# PGTN021_octasource2b_controls.net
KiCad netlist of a schematic drawn in EAGLE
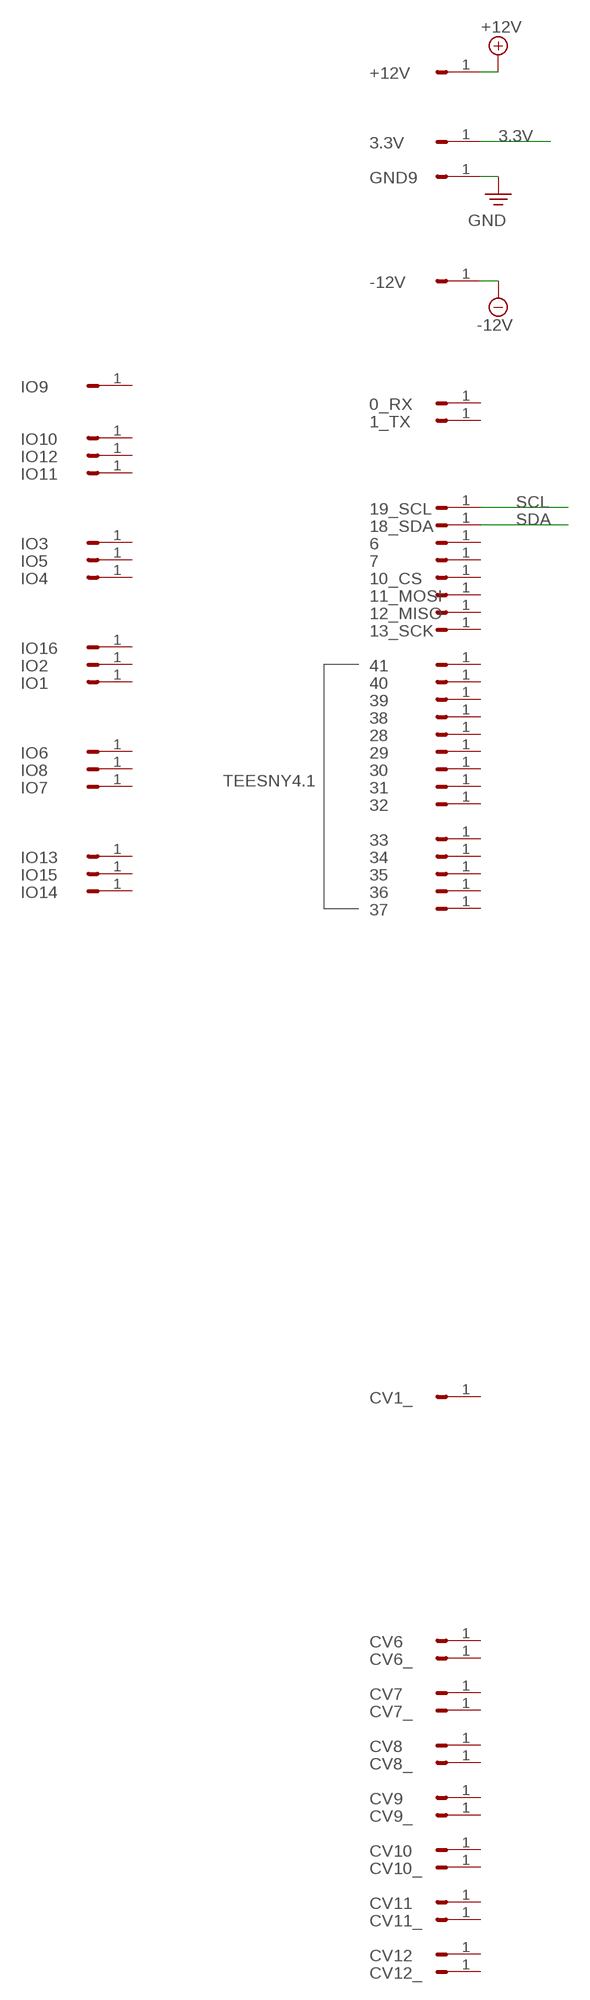
[diagram p0: schematic, sheet 1, part 1 of 2]
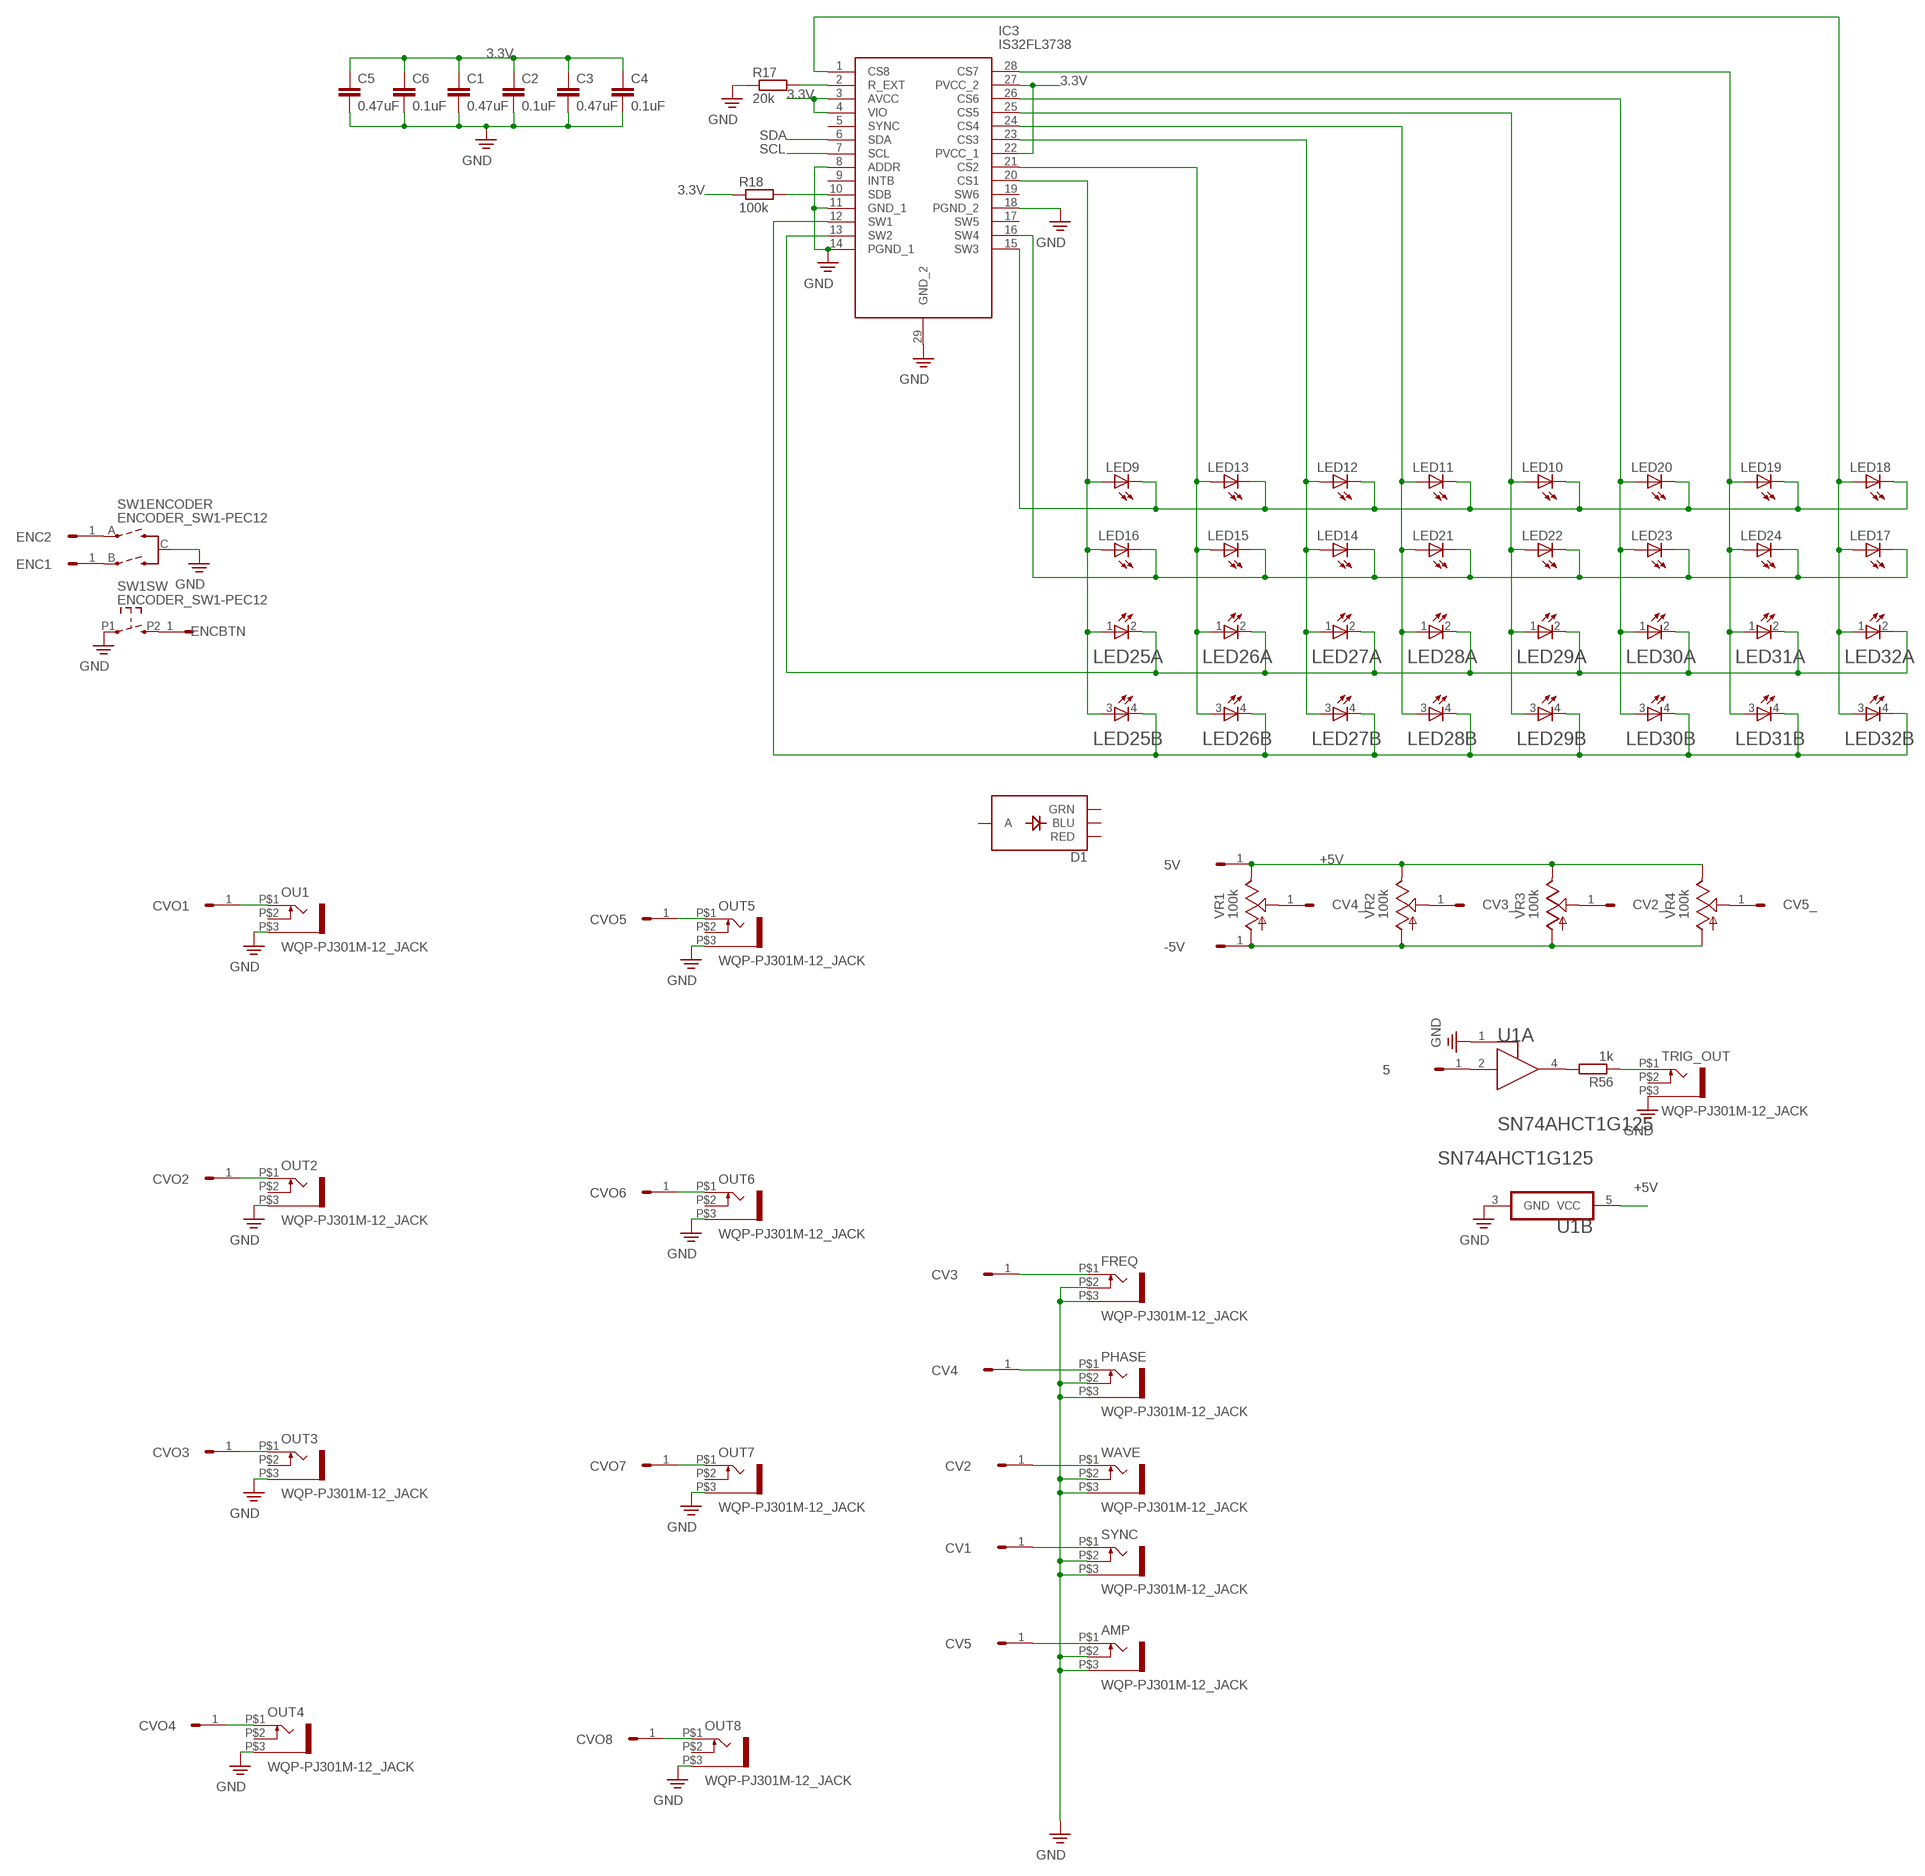
[diagram p1: schematic, sheet 1, part 2 of 2]

(export (version "E")
  (design (tool "Eeschema 10.0.6"))
  (components
    (comp (ref "+12V")
      (value "HEADER/MALE/01")
      (footprint "eagle-import:HEADER_MALE_01")
      (fields (field (name "SPICEPREFIX") "X"))
      (libsource (lib "eagle-import") (part "HEADER/MALE/01"))
    )
    (comp (ref "-5V")
      (value "HEADER/MALE/01")
      (footprint "eagle-import:HEADER_MALE_01")
      (fields (field (name "SPICEPREFIX") "X"))
      (libsource (lib "eagle-import") (part "HEADER/MALE/01"))
    )
    (comp (ref "-12V")
      (value "HEADER/MALE/01")
      (footprint "eagle-import:HEADER_MALE_01")
      (fields (field (name "SPICEPREFIX") "X"))
      (libsource (lib "eagle-import") (part "HEADER/MALE/01"))
    )
    (comp (ref "0_RX")
      (value "HEADER/MALE/01")
      (footprint "eagle-import:HEADER_MALE_01")
      (fields (field (name "SPICEPREFIX") "X"))
      (libsource (lib "eagle-import") (part "HEADER/MALE/01"))
    )
    (comp (ref "1_TX")
      (value "HEADER/MALE/01")
      (footprint "eagle-import:HEADER_MALE_01")
      (fields (field (name "SPICEPREFIX") "X"))
      (libsource (lib "eagle-import") (part "HEADER/MALE/01"))
    )
    (comp (ref "3.3V")
      (value "HEADER/MALE/01")
      (footprint "eagle-import:HEADER_MALE_01")
      (fields (field (name "SPICEPREFIX") "X"))
      (libsource (lib "eagle-import") (part "HEADER/MALE/01"))
    )
    (comp (ref "5")
      (value "HEADER/MALE/01")
      (footprint "eagle-import:HEADER_MALE_01")
      (fields (field (name "SPICEPREFIX") "X"))
      (libsource (lib "eagle-import") (part "HEADER/MALE/01"))
    )
    (comp (ref "5V")
      (value "HEADER/MALE/01")
      (footprint "eagle-import:HEADER_MALE_01")
      (fields (field (name "SPICEPREFIX") "X"))
      (libsource (lib "eagle-import") (part "HEADER/MALE/01"))
    )
    (comp (ref "6")
      (value "HEADER/MALE/01")
      (footprint "eagle-import:HEADER_MALE_01")
      (fields (field (name "SPICEPREFIX") "X"))
      (libsource (lib "eagle-import") (part "HEADER/MALE/01"))
    )
    (comp (ref "7")
      (value "HEADER/MALE/01")
      (footprint "eagle-import:HEADER_MALE_01")
      (fields (field (name "SPICEPREFIX") "X"))
      (libsource (lib "eagle-import") (part "HEADER/MALE/01"))
    )
    (comp (ref "10_CS")
      (value "HEADER/MALE/01")
      (footprint "eagle-import:HEADER_MALE_01")
      (fields (field (name "SPICEPREFIX") "X"))
      (libsource (lib "eagle-import") (part "HEADER/MALE/01"))
    )
    (comp (ref "11_MOSI")
      (value "HEADER/MALE/01")
      (footprint "eagle-import:HEADER_MALE_01")
      (fields (field (name "SPICEPREFIX") "X"))
      (libsource (lib "eagle-import") (part "HEADER/MALE/01"))
    )
    (comp (ref "12_MISO")
      (value "HEADER/MALE/01")
      (footprint "eagle-import:HEADER_MALE_01")
      (fields (field (name "SPICEPREFIX") "X"))
      (libsource (lib "eagle-import") (part "HEADER/MALE/01"))
    )
    (comp (ref "13_SCK")
      (value "HEADER/MALE/01")
      (footprint "eagle-import:HEADER_MALE_01")
      (fields (field (name "SPICEPREFIX") "X"))
      (libsource (lib "eagle-import") (part "HEADER/MALE/01"))
    )
    (comp (ref "18_SDA")
      (value "HEADER/MALE/01")
      (footprint "eagle-import:HEADER_MALE_01")
      (fields (field (name "SPICEPREFIX") "X"))
      (libsource (lib "eagle-import") (part "HEADER/MALE/01"))
    )
    (comp (ref "19_SCL")
      (value "HEADER/MALE/01")
      (footprint "eagle-import:HEADER_MALE_01")
      (fields (field (name "SPICEPREFIX") "X"))
      (libsource (lib "eagle-import") (part "HEADER/MALE/01"))
    )
    (comp (ref "28")
      (value "HEADER/MALE/01")
      (footprint "eagle-import:HEADER_MALE_01")
      (fields (field (name "SPICEPREFIX") "X"))
      (libsource (lib "eagle-import") (part "HEADER/MALE/01"))
    )
    (comp (ref "29")
      (value "HEADER/MALE/01")
      (footprint "eagle-import:HEADER_MALE_01")
      (fields (field (name "SPICEPREFIX") "X"))
      (libsource (lib "eagle-import") (part "HEADER/MALE/01"))
    )
    (comp (ref "30")
      (value "HEADER/MALE/01")
      (footprint "eagle-import:HEADER_MALE_01")
      (fields (field (name "SPICEPREFIX") "X"))
      (libsource (lib "eagle-import") (part "HEADER/MALE/01"))
    )
    (comp (ref "31")
      (value "HEADER/MALE/01")
      (footprint "eagle-import:HEADER_MALE_01")
      (fields (field (name "SPICEPREFIX") "X"))
      (libsource (lib "eagle-import") (part "HEADER/MALE/01"))
    )
    (comp (ref "32")
      (value "HEADER/MALE/01")
      (footprint "eagle-import:HEADER_MALE_01")
      (fields (field (name "SPICEPREFIX") "X"))
      (libsource (lib "eagle-import") (part "HEADER/MALE/01"))
    )
    (comp (ref "33")
      (value "HEADER/MALE/01")
      (footprint "eagle-import:HEADER_MALE_01")
      (fields (field (name "SPICEPREFIX") "X"))
      (libsource (lib "eagle-import") (part "HEADER/MALE/01"))
    )
    (comp (ref "34")
      (value "HEADER/MALE/01")
      (footprint "eagle-import:HEADER_MALE_01")
      (fields (field (name "SPICEPREFIX") "X"))
      (libsource (lib "eagle-import") (part "HEADER/MALE/01"))
    )
    (comp (ref "35")
      (value "HEADER/MALE/01")
      (footprint "eagle-import:HEADER_MALE_01")
      (fields (field (name "SPICEPREFIX") "X"))
      (libsource (lib "eagle-import") (part "HEADER/MALE/01"))
    )
    (comp (ref "36")
      (value "HEADER/MALE/01")
      (footprint "eagle-import:HEADER_MALE_01")
      (fields (field (name "SPICEPREFIX") "X"))
      (libsource (lib "eagle-import") (part "HEADER/MALE/01"))
    )
    (comp (ref "37")
      (value "HEADER/MALE/01")
      (footprint "eagle-import:HEADER_MALE_01")
      (fields (field (name "SPICEPREFIX") "X"))
      (libsource (lib "eagle-import") (part "HEADER/MALE/01"))
    )
    (comp (ref "38")
      (value "HEADER/MALE/01")
      (footprint "eagle-import:HEADER_MALE_01")
      (fields (field (name "SPICEPREFIX") "X"))
      (libsource (lib "eagle-import") (part "HEADER/MALE/01"))
    )
    (comp (ref "39")
      (value "HEADER/MALE/01")
      (footprint "eagle-import:HEADER_MALE_01")
      (fields (field (name "SPICEPREFIX") "X"))
      (libsource (lib "eagle-import") (part "HEADER/MALE/01"))
    )
    (comp (ref "40")
      (value "HEADER/MALE/01")
      (footprint "eagle-import:HEADER_MALE_01")
      (fields (field (name "SPICEPREFIX") "X"))
      (libsource (lib "eagle-import") (part "HEADER/MALE/01"))
    )
    (comp (ref "41")
      (value "HEADER/MALE/01")
      (footprint "eagle-import:HEADER_MALE_01")
      (fields (field (name "SPICEPREFIX") "X"))
      (libsource (lib "eagle-import") (part "HEADER/MALE/01"))
    )
    (comp (ref "AMP")
      (value "WQP-PJ301M-12_JACK")
      (footprint "eagle-import:WQP-PJ301M-12_JACK")
      (libsource (lib "eagle-import") (part "WQP-PJ301M-12_JACK"))
    )
    (comp (ref "C1")
      (value "0.47uF")
      (footprint "eagle-import:C0603")
      (libsource (lib "eagle-import") (part "CAPACITORC0603"))
    )
    (comp (ref "C2")
      (value "0.1uF")
      (footprint "eagle-import:C0603")
      (libsource (lib "eagle-import") (part "CAPACITORC0603"))
    )
    (comp (ref "C3")
      (value "0.47uF")
      (footprint "eagle-import:C0603")
      (libsource (lib "eagle-import") (part "CAPACITORC0603"))
    )
    (comp (ref "C4")
      (value "0.1uF")
      (footprint "eagle-import:C0603")
      (libsource (lib "eagle-import") (part "CAPACITORC0603"))
    )
    (comp (ref "C5")
      (value "0.47uF")
      (footprint "eagle-import:C0603")
      (libsource (lib "eagle-import") (part "CAPACITORC0603"))
    )
    (comp (ref "C6")
      (value "0.1uF")
      (footprint "eagle-import:C0603")
      (libsource (lib "eagle-import") (part "CAPACITORC0603"))
    )
    (comp (ref "CV1")
      (value "HEADER/MALE/01")
      (footprint "eagle-import:HEADER_MALE_01")
      (fields (field (name "SPICEPREFIX") "X"))
      (libsource (lib "eagle-import") (part "HEADER/MALE/01"))
    )
    (comp (ref "CV1_")
      (value "HEADER/MALE/01")
      (footprint "eagle-import:HEADER_MALE_01")
      (fields (field (name "SPICEPREFIX") "X"))
      (libsource (lib "eagle-import") (part "HEADER/MALE/01"))
    )
    (comp (ref "CV2")
      (value "HEADER/MALE/01")
      (footprint "eagle-import:HEADER_MALE_01")
      (fields (field (name "SPICEPREFIX") "X"))
      (libsource (lib "eagle-import") (part "HEADER/MALE/01"))
    )
    (comp (ref "CV2_")
      (value "HEADER/MALE/01")
      (footprint "eagle-import:HEADER_MALE_01")
      (fields (field (name "SPICEPREFIX") "X"))
      (libsource (lib "eagle-import") (part "HEADER/MALE/01"))
    )
    (comp (ref "CV3")
      (value "HEADER/MALE/01")
      (footprint "eagle-import:HEADER_MALE_01")
      (fields (field (name "SPICEPREFIX") "X"))
      (libsource (lib "eagle-import") (part "HEADER/MALE/01"))
    )
    (comp (ref "CV3_")
      (value "HEADER/MALE/01")
      (footprint "eagle-import:HEADER_MALE_01")
      (fields (field (name "SPICEPREFIX") "X"))
      (libsource (lib "eagle-import") (part "HEADER/MALE/01"))
    )
    (comp (ref "CV4")
      (value "HEADER/MALE/01")
      (footprint "eagle-import:HEADER_MALE_01")
      (fields (field (name "SPICEPREFIX") "X"))
      (libsource (lib "eagle-import") (part "HEADER/MALE/01"))
    )
    (comp (ref "CV4_")
      (value "HEADER/MALE/01")
      (footprint "eagle-import:HEADER_MALE_01")
      (fields (field (name "SPICEPREFIX") "X"))
      (libsource (lib "eagle-import") (part "HEADER/MALE/01"))
    )
    (comp (ref "CV5")
      (value "HEADER/MALE/01")
      (footprint "eagle-import:HEADER_MALE_01")
      (fields (field (name "SPICEPREFIX") "X"))
      (libsource (lib "eagle-import") (part "HEADER/MALE/01"))
    )
    (comp (ref "CV5_")
      (value "HEADER/MALE/01")
      (footprint "eagle-import:HEADER_MALE_01")
      (fields (field (name "SPICEPREFIX") "X"))
      (libsource (lib "eagle-import") (part "HEADER/MALE/01"))
    )
    (comp (ref "CV6")
      (value "HEADER/MALE/01")
      (footprint "eagle-import:HEADER_MALE_01")
      (fields (field (name "SPICEPREFIX") "X"))
      (libsource (lib "eagle-import") (part "HEADER/MALE/01"))
    )
    (comp (ref "CV6_")
      (value "HEADER/MALE/01")
      (footprint "eagle-import:HEADER_MALE_01")
      (fields (field (name "SPICEPREFIX") "X"))
      (libsource (lib "eagle-import") (part "HEADER/MALE/01"))
    )
    (comp (ref "CV7")
      (value "HEADER/MALE/01")
      (footprint "eagle-import:HEADER_MALE_01")
      (fields (field (name "SPICEPREFIX") "X"))
      (libsource (lib "eagle-import") (part "HEADER/MALE/01"))
    )
    (comp (ref "CV7_")
      (value "HEADER/MALE/01")
      (footprint "eagle-import:HEADER_MALE_01")
      (fields (field (name "SPICEPREFIX") "X"))
      (libsource (lib "eagle-import") (part "HEADER/MALE/01"))
    )
    (comp (ref "CV8")
      (value "HEADER/MALE/01")
      (footprint "eagle-import:HEADER_MALE_01")
      (fields (field (name "SPICEPREFIX") "X"))
      (libsource (lib "eagle-import") (part "HEADER/MALE/01"))
    )
    (comp (ref "CV8_")
      (value "HEADER/MALE/01")
      (footprint "eagle-import:HEADER_MALE_01")
      (fields (field (name "SPICEPREFIX") "X"))
      (libsource (lib "eagle-import") (part "HEADER/MALE/01"))
    )
    (comp (ref "CV9")
      (value "HEADER/MALE/01")
      (footprint "eagle-import:HEADER_MALE_01")
      (fields (field (name "SPICEPREFIX") "X"))
      (libsource (lib "eagle-import") (part "HEADER/MALE/01"))
    )
    (comp (ref "CV9_")
      (value "HEADER/MALE/01")
      (footprint "eagle-import:HEADER_MALE_01")
      (fields (field (name "SPICEPREFIX") "X"))
      (libsource (lib "eagle-import") (part "HEADER/MALE/01"))
    )
    (comp (ref "CV10")
      (value "HEADER/MALE/01")
      (footprint "eagle-import:HEADER_MALE_01")
      (fields (field (name "SPICEPREFIX") "X"))
      (libsource (lib "eagle-import") (part "HEADER/MALE/01"))
    )
    (comp (ref "CV10_")
      (value "HEADER/MALE/01")
      (footprint "eagle-import:HEADER_MALE_01")
      (fields (field (name "SPICEPREFIX") "X"))
      (libsource (lib "eagle-import") (part "HEADER/MALE/01"))
    )
    (comp (ref "CV11")
      (value "HEADER/MALE/01")
      (footprint "eagle-import:HEADER_MALE_01")
      (fields (field (name "SPICEPREFIX") "X"))
      (libsource (lib "eagle-import") (part "HEADER/MALE/01"))
    )
    (comp (ref "CV11_")
      (value "HEADER/MALE/01")
      (footprint "eagle-import:HEADER_MALE_01")
      (fields (field (name "SPICEPREFIX") "X"))
      (libsource (lib "eagle-import") (part "HEADER/MALE/01"))
    )
    (comp (ref "CV12")
      (value "HEADER/MALE/01")
      (footprint "eagle-import:HEADER_MALE_01")
      (fields (field (name "SPICEPREFIX") "X"))
      (libsource (lib "eagle-import") (part "HEADER/MALE/01"))
    )
    (comp (ref "CV12_")
      (value "HEADER/MALE/01")
      (footprint "eagle-import:HEADER_MALE_01")
      (fields (field (name "SPICEPREFIX") "X"))
      (libsource (lib "eagle-import") (part "HEADER/MALE/01"))
    )
    (comp (ref "CVO1")
      (value "HEADER/MALE/01")
      (footprint "eagle-import:HEADER_MALE_01")
      (fields (field (name "SPICEPREFIX") "X"))
      (libsource (lib "eagle-import") (part "HEADER/MALE/01"))
    )
    (comp (ref "CVO2")
      (value "HEADER/MALE/01")
      (footprint "eagle-import:HEADER_MALE_01")
      (fields (field (name "SPICEPREFIX") "X"))
      (libsource (lib "eagle-import") (part "HEADER/MALE/01"))
    )
    (comp (ref "CVO3")
      (value "HEADER/MALE/01")
      (footprint "eagle-import:HEADER_MALE_01")
      (fields (field (name "SPICEPREFIX") "X"))
      (libsource (lib "eagle-import") (part "HEADER/MALE/01"))
    )
    (comp (ref "CVO4")
      (value "HEADER/MALE/01")
      (footprint "eagle-import:HEADER_MALE_01")
      (fields (field (name "SPICEPREFIX") "X"))
      (libsource (lib "eagle-import") (part "HEADER/MALE/01"))
    )
    (comp (ref "CVO5")
      (value "HEADER/MALE/01")
      (footprint "eagle-import:HEADER_MALE_01")
      (fields (field (name "SPICEPREFIX") "X"))
      (libsource (lib "eagle-import") (part "HEADER/MALE/01"))
    )
    (comp (ref "CVO6")
      (value "HEADER/MALE/01")
      (footprint "eagle-import:HEADER_MALE_01")
      (fields (field (name "SPICEPREFIX") "X"))
      (libsource (lib "eagle-import") (part "HEADER/MALE/01"))
    )
    (comp (ref "CVO7")
      (value "HEADER/MALE/01")
      (footprint "eagle-import:HEADER_MALE_01")
      (fields (field (name "SPICEPREFIX") "X"))
      (libsource (lib "eagle-import") (part "HEADER/MALE/01"))
    )
    (comp (ref "CVO8")
      (value "HEADER/MALE/01")
      (footprint "eagle-import:HEADER_MALE_01")
      (fields (field (name "SPICEPREFIX") "X"))
      (libsource (lib "eagle-import") (part "HEADER/MALE/01"))
    )
    (comp (ref "D1")
      (value "LED-RGB-CADIALIGHT1210")
      (footprint "eagle-import:CHIPLED_1210")
      (libsource (lib "eagle-import") (part "LED-RGB-CADIALIGHT1210"))
    )
    (comp (ref "ENC1")
      (value "HEADER/MALE/01")
      (footprint "eagle-import:HEADER_MALE_01")
      (fields (field (name "SPICEPREFIX") "X"))
      (libsource (lib "eagle-import") (part "HEADER/MALE/01"))
    )
    (comp (ref "ENC2")
      (value "HEADER/MALE/01")
      (footprint "eagle-import:HEADER_MALE_01")
      (fields (field (name "SPICEPREFIX") "X"))
      (libsource (lib "eagle-import") (part "HEADER/MALE/01"))
    )
    (comp (ref "ENCBTN")
      (value "HEADER/MALE/01")
      (footprint "eagle-import:HEADER_MALE_01")
      (fields (field (name "SPICEPREFIX") "X"))
      (libsource (lib "eagle-import") (part "HEADER/MALE/01"))
    )
    (comp (ref "FREQ")
      (value "WQP-PJ301M-12_JACK")
      (footprint "eagle-import:WQP-PJ301M-12_JACK")
      (libsource (lib "eagle-import") (part "WQP-PJ301M-12_JACK"))
    )
    (comp (ref "GND9")
      (value "HEADER/MALE/01")
      (footprint "eagle-import:HEADER_MALE_01")
      (fields (field (name "SPICEPREFIX") "X"))
      (libsource (lib "eagle-import") (part "HEADER/MALE/01"))
    )
    (comp (ref "IC3")
      (value "IS32FL3738")
      (footprint "eagle-import:TSSOP29")
      (fields (field (name "MANUFACTURER_PART_NUMBER") "IS32FL3738-ZLA3-TR"))
      (libsource (lib "eagle-import") (part "IS32FL3738"))
    )
    (comp (ref "IO1")
      (value "HEADER/MALE/01")
      (footprint "eagle-import:HEADER_MALE_01")
      (fields (field (name "SPICEPREFIX") "X"))
      (libsource (lib "eagle-import") (part "HEADER/MALE/01"))
    )
    (comp (ref "IO2")
      (value "HEADER/MALE/01")
      (footprint "eagle-import:HEADER_MALE_01")
      (fields (field (name "SPICEPREFIX") "X"))
      (libsource (lib "eagle-import") (part "HEADER/MALE/01"))
    )
    (comp (ref "IO3")
      (value "HEADER/MALE/01")
      (footprint "eagle-import:HEADER_MALE_01")
      (fields (field (name "SPICEPREFIX") "X"))
      (libsource (lib "eagle-import") (part "HEADER/MALE/01"))
    )
    (comp (ref "IO4")
      (value "HEADER/MALE/01")
      (footprint "eagle-import:HEADER_MALE_01")
      (fields (field (name "SPICEPREFIX") "X"))
      (libsource (lib "eagle-import") (part "HEADER/MALE/01"))
    )
    (comp (ref "IO5")
      (value "HEADER/MALE/01")
      (footprint "eagle-import:HEADER_MALE_01")
      (fields (field (name "SPICEPREFIX") "X"))
      (libsource (lib "eagle-import") (part "HEADER/MALE/01"))
    )
    (comp (ref "IO6")
      (value "HEADER/MALE/01")
      (footprint "eagle-import:HEADER_MALE_01")
      (fields (field (name "SPICEPREFIX") "X"))
      (libsource (lib "eagle-import") (part "HEADER/MALE/01"))
    )
    (comp (ref "IO7")
      (value "HEADER/MALE/01")
      (footprint "eagle-import:HEADER_MALE_01")
      (fields (field (name "SPICEPREFIX") "X"))
      (libsource (lib "eagle-import") (part "HEADER/MALE/01"))
    )
    (comp (ref "IO8")
      (value "HEADER/MALE/01")
      (footprint "eagle-import:HEADER_MALE_01")
      (fields (field (name "SPICEPREFIX") "X"))
      (libsource (lib "eagle-import") (part "HEADER/MALE/01"))
    )
    (comp (ref "IO9")
      (value "HEADER/MALE/01")
      (footprint "eagle-import:HEADER_MALE_01")
      (fields (field (name "SPICEPREFIX") "X"))
      (libsource (lib "eagle-import") (part "HEADER/MALE/01"))
    )
    (comp (ref "IO10")
      (value "HEADER/MALE/01")
      (footprint "eagle-import:HEADER_MALE_01")
      (fields (field (name "SPICEPREFIX") "X"))
      (libsource (lib "eagle-import") (part "HEADER/MALE/01"))
    )
    (comp (ref "IO11")
      (value "HEADER/MALE/01")
      (footprint "eagle-import:HEADER_MALE_01")
      (fields (field (name "SPICEPREFIX") "X"))
      (libsource (lib "eagle-import") (part "HEADER/MALE/01"))
    )
    (comp (ref "IO12")
      (value "HEADER/MALE/01")
      (footprint "eagle-import:HEADER_MALE_01")
      (fields (field (name "SPICEPREFIX") "X"))
      (libsource (lib "eagle-import") (part "HEADER/MALE/01"))
    )
    (comp (ref "IO13")
      (value "HEADER/MALE/01")
      (footprint "eagle-import:HEADER_MALE_01")
      (fields (field (name "SPICEPREFIX") "X"))
      (libsource (lib "eagle-import") (part "HEADER/MALE/01"))
    )
    (comp (ref "IO14")
      (value "HEADER/MALE/01")
      (footprint "eagle-import:HEADER_MALE_01")
      (fields (field (name "SPICEPREFIX") "X"))
      (libsource (lib "eagle-import") (part "HEADER/MALE/01"))
    )
    (comp (ref "IO15")
      (value "HEADER/MALE/01")
      (footprint "eagle-import:HEADER_MALE_01")
      (fields (field (name "SPICEPREFIX") "X"))
      (libsource (lib "eagle-import") (part "HEADER/MALE/01"))
    )
    (comp (ref "IO16")
      (value "HEADER/MALE/01")
      (footprint "eagle-import:HEADER_MALE_01")
      (fields (field (name "SPICEPREFIX") "X"))
      (libsource (lib "eagle-import") (part "HEADER/MALE/01"))
    )
    (comp (ref "LED9")
      (value "LEDCHIPLED_0805")
      (footprint "eagle-import:CHIPLED_0805")
      (libsource (lib "eagle-import") (part "LEDCHIPLED_0805"))
    )
    (comp (ref "LED10")
      (value "LEDCHIPLED_0805")
      (footprint "eagle-import:CHIPLED_0805")
      (libsource (lib "eagle-import") (part "LEDCHIPLED_0805"))
    )
    (comp (ref "LED11")
      (value "LEDCHIPLED_0805")
      (footprint "eagle-import:CHIPLED_0805")
      (libsource (lib "eagle-import") (part "LEDCHIPLED_0805"))
    )
    (comp (ref "LED12")
      (value "LEDCHIPLED_0805")
      (footprint "eagle-import:CHIPLED_0805")
      (libsource (lib "eagle-import") (part "LEDCHIPLED_0805"))
    )
    (comp (ref "LED13")
      (value "LEDCHIPLED_0805")
      (footprint "eagle-import:CHIPLED_0805")
      (libsource (lib "eagle-import") (part "LEDCHIPLED_0805"))
    )
    (comp (ref "LED14")
      (value "LEDCHIPLED_0805")
      (footprint "eagle-import:CHIPLED_0805")
      (libsource (lib "eagle-import") (part "LEDCHIPLED_0805"))
    )
    (comp (ref "LED15")
      (value "LEDCHIPLED_0805")
      (footprint "eagle-import:CHIPLED_0805")
      (libsource (lib "eagle-import") (part "LEDCHIPLED_0805"))
    )
    (comp (ref "LED16")
      (value "LEDCHIPLED_0805")
      (footprint "eagle-import:CHIPLED_0805")
      (libsource (lib "eagle-import") (part "LEDCHIPLED_0805"))
    )
    (comp (ref "LED17")
      (value "LEDCHIPLED_0805")
      (footprint "eagle-import:CHIPLED_0805")
      (libsource (lib "eagle-import") (part "LEDCHIPLED_0805"))
    )
    (comp (ref "LED18")
      (value "LEDCHIPLED_0805")
      (footprint "eagle-import:CHIPLED_0805")
      (libsource (lib "eagle-import") (part "LEDCHIPLED_0805"))
    )
    (comp (ref "LED19")
      (value "LEDCHIPLED_0805")
      (footprint "eagle-import:CHIPLED_0805")
      (libsource (lib "eagle-import") (part "LEDCHIPLED_0805"))
    )
    (comp (ref "LED20")
      (value "LEDCHIPLED_0805")
      (footprint "eagle-import:CHIPLED_0805")
      (libsource (lib "eagle-import") (part "LEDCHIPLED_0805"))
    )
    (comp (ref "LED21")
      (value "LEDCHIPLED_0805")
      (footprint "eagle-import:CHIPLED_0805")
      (libsource (lib "eagle-import") (part "LEDCHIPLED_0805"))
    )
    (comp (ref "LED22")
      (value "LEDCHIPLED_0805")
      (footprint "eagle-import:CHIPLED_0805")
      (libsource (lib "eagle-import") (part "LEDCHIPLED_0805"))
    )
    (comp (ref "LED23")
      (value "LEDCHIPLED_0805")
      (footprint "eagle-import:CHIPLED_0805")
      (libsource (lib "eagle-import") (part "LEDCHIPLED_0805"))
    )
    (comp (ref "LED24")
      (value "LEDCHIPLED_0805")
      (footprint "eagle-import:CHIPLED_0805")
      (libsource (lib "eagle-import") (part "LEDCHIPLED_0805"))
    )
    (comp (ref "LED25")
      (value "LED-BICOLOUR")
      (footprint "eagle-import:CHIPLED_1210")
      (fields
        (field (name "DIGIKEY_PART_NUMBER") "350-2083-1-ND")
        (field (name "MF") "Dialight")
        (field (name "MOUSER_PART_NUMBER") "645-598-8640-207F")
      )
      (libsource (lib "eagle-import") (part "LED-BICOLOUR"))
    )
    (comp (ref "LED26")
      (value "LED-BICOLOUR")
      (footprint "eagle-import:CHIPLED_1210")
      (fields
        (field (name "DIGIKEY_PART_NUMBER") "350-2083-1-ND")
        (field (name "MF") "Dialight")
        (field (name "MOUSER_PART_NUMBER") "645-598-8640-207F")
      )
      (libsource (lib "eagle-import") (part "LED-BICOLOUR"))
    )
    (comp (ref "LED27")
      (value "LED-BICOLOUR")
      (footprint "eagle-import:CHIPLED_1210")
      (fields
        (field (name "DIGIKEY_PART_NUMBER") "350-2083-1-ND")
        (field (name "MF") "Dialight")
        (field (name "MOUSER_PART_NUMBER") "645-598-8640-207F")
      )
      (libsource (lib "eagle-import") (part "LED-BICOLOUR"))
    )
    (comp (ref "LED28")
      (value "LED-BICOLOUR")
      (footprint "eagle-import:CHIPLED_1210")
      (fields
        (field (name "DIGIKEY_PART_NUMBER") "350-2083-1-ND")
        (field (name "MF") "Dialight")
        (field (name "MOUSER_PART_NUMBER") "645-598-8640-207F")
      )
      (libsource (lib "eagle-import") (part "LED-BICOLOUR"))
    )
    (comp (ref "LED29")
      (value "LED-BICOLOUR")
      (footprint "eagle-import:CHIPLED_1210")
      (fields
        (field (name "DIGIKEY_PART_NUMBER") "350-2083-1-ND")
        (field (name "MF") "Dialight")
        (field (name "MOUSER_PART_NUMBER") "645-598-8640-207F")
      )
      (libsource (lib "eagle-import") (part "LED-BICOLOUR"))
    )
    (comp (ref "LED30")
      (value "LED-BICOLOUR")
      (footprint "eagle-import:CHIPLED_1210")
      (fields
        (field (name "DIGIKEY_PART_NUMBER") "350-2083-1-ND")
        (field (name "MF") "Dialight")
        (field (name "MOUSER_PART_NUMBER") "645-598-8640-207F")
      )
      (libsource (lib "eagle-import") (part "LED-BICOLOUR"))
    )
    (comp (ref "LED31")
      (value "LED-BICOLOUR")
      (footprint "eagle-import:CHIPLED_1210")
      (fields
        (field (name "DIGIKEY_PART_NUMBER") "350-2083-1-ND")
        (field (name "MF") "Dialight")
        (field (name "MOUSER_PART_NUMBER") "645-598-8640-207F")
      )
      (libsource (lib "eagle-import") (part "LED-BICOLOUR"))
    )
    (comp (ref "LED32")
      (value "LED-BICOLOUR")
      (footprint "eagle-import:CHIPLED_1210")
      (fields
        (field (name "DIGIKEY_PART_NUMBER") "350-2083-1-ND")
        (field (name "MF") "Dialight")
        (field (name "MOUSER_PART_NUMBER") "645-598-8640-207F")
      )
      (libsource (lib "eagle-import") (part "LED-BICOLOUR"))
    )
    (comp (ref "OU1")
      (value "WQP-PJ301M-12_JACK")
      (footprint "eagle-import:WQP-PJ301M-12_JACK")
      (libsource (lib "eagle-import") (part "WQP-PJ301M-12_JACK"))
    )
    (comp (ref "OUT2")
      (value "WQP-PJ301M-12_JACK")
      (footprint "eagle-import:WQP-PJ301M-12_JACK")
      (libsource (lib "eagle-import") (part "WQP-PJ301M-12_JACK"))
    )
    (comp (ref "OUT3")
      (value "WQP-PJ301M-12_JACK")
      (footprint "eagle-import:WQP-PJ301M-12_JACK")
      (libsource (lib "eagle-import") (part "WQP-PJ301M-12_JACK"))
    )
    (comp (ref "OUT4")
      (value "WQP-PJ301M-12_JACK")
      (footprint "eagle-import:WQP-PJ301M-12_JACK")
      (libsource (lib "eagle-import") (part "WQP-PJ301M-12_JACK"))
    )
    (comp (ref "OUT5")
      (value "WQP-PJ301M-12_JACK")
      (footprint "eagle-import:WQP-PJ301M-12_JACK")
      (libsource (lib "eagle-import") (part "WQP-PJ301M-12_JACK"))
    )
    (comp (ref "OUT6")
      (value "WQP-PJ301M-12_JACK")
      (footprint "eagle-import:WQP-PJ301M-12_JACK")
      (libsource (lib "eagle-import") (part "WQP-PJ301M-12_JACK"))
    )
    (comp (ref "OUT7")
      (value "WQP-PJ301M-12_JACK")
      (footprint "eagle-import:WQP-PJ301M-12_JACK")
      (libsource (lib "eagle-import") (part "WQP-PJ301M-12_JACK"))
    )
    (comp (ref "OUT8")
      (value "WQP-PJ301M-12_JACK")
      (footprint "eagle-import:WQP-PJ301M-12_JACK")
      (libsource (lib "eagle-import") (part "WQP-PJ301M-12_JACK"))
    )
    (comp (ref "PHASE")
      (value "WQP-PJ301M-12_JACK")
      (footprint "eagle-import:WQP-PJ301M-12_JACK")
      (libsource (lib "eagle-import") (part "WQP-PJ301M-12_JACK"))
    )
    (comp (ref "R17")
      (value "20k")
      (footprint "eagle-import:R0603")
      (libsource (lib "eagle-import") (part "RESISTOR"))
    )
    (comp (ref "R18")
      (value "100k")
      (footprint "eagle-import:R0603")
      (libsource (lib "eagle-import") (part "RESISTOR"))
    )
    (comp (ref "R56")
      (value "1k")
      (footprint "eagle-import:R0603")
      (libsource (lib "eagle-import") (part "RESISTOR"))
    )
    (comp (ref "SW1")
      (value "ENCODER_SW1-PEC12")
      (footprint "eagle-import:PEC12_INCREMENTAL_ENCODER")
      (libsource (lib "eagle-import") (part "ENCODER_SW1-PEC12"))
    )
    (comp (ref "SYNC")
      (value "WQP-PJ301M-12_JACK")
      (footprint "eagle-import:WQP-PJ301M-12_JACK")
      (libsource (lib "eagle-import") (part "WQP-PJ301M-12_JACK"))
    )
    (comp (ref "TRIG_OUT")
      (value "WQP-PJ301M-12_JACK")
      (footprint "eagle-import:WQP-PJ301M-12_JACK")
      (libsource (lib "eagle-import") (part "WQP-PJ301M-12_JACK"))
    )
    (comp (ref "U1")
      (value "74AHCT1G125\"")
      (footprint "eagle-import:74AHCT1G125")
      (fields (field (name "MF") "Texas Instruments") (field (name "MPN") "SN74AHCT1G125"))
      (libsource (lib "eagle-import") (part "74AHCT1G125{dblquote}"))
    )
    (comp (ref "VR1")
      (value "100k")
      (footprint "eagle-import:9MM_SNAP-IN_POT")
      (libsource (lib "eagle-import") (part "9MM_SNAP-IN_POT_"))
    )
    (comp (ref "VR2")
      (value "100k")
      (footprint "eagle-import:9MM_SNAP-IN_POT")
      (libsource (lib "eagle-import") (part "9MM_SNAP-IN_POT_"))
    )
    (comp (ref "VR3")
      (value "100k")
      (footprint "eagle-import:9MM_SNAP-IN_POT")
      (libsource (lib "eagle-import") (part "9MM_SNAP-IN_POT_"))
    )
    (comp (ref "VR4")
      (value "100k")
      (footprint "eagle-import:9MM_SNAP-IN_POT")
      (libsource (lib "eagle-import") (part "9MM_SNAP-IN_POT_"))
    )
    (comp (ref "WAVE")
      (value "WQP-PJ301M-12_JACK")
      (footprint "eagle-import:WQP-PJ301M-12_JACK")
      (libsource (lib "eagle-import") (part "WQP-PJ301M-12_JACK"))
    )
  )
  (nets
    (net (code "1") (name "+12V") (class "Default")
      (node (ref "+12V") (pin "1") (pinfunction "3_1") (pintype "passive"))
    )
    (net (code "2") (name "-12V") (class "Default")
      (node (ref "-12V") (pin "1") (pinfunction "3_1") (pintype "passive"))
    )
    (net (code "3") (name "/+5V") (class "Default")
      (node (ref "5V") (pin "1") (pinfunction "3_1") (pintype "passive"))
      (node (ref "U1") (pin "5") (pinfunction "VCC_5") (pintype "power_in"))
      (node (ref "VR1") (pin "3") (pinfunction "E_3") (pintype "passive"))
      (node (ref "VR2") (pin "3") (pinfunction "E_3") (pintype "passive"))
      (node (ref "VR3") (pin "3") (pinfunction "E_3") (pintype "passive"))
      (node (ref "VR4") (pin "3") (pinfunction "E_3") (pintype "passive"))
    )
    (net (code "4") (name "/3.3V") (class "Default")
      (node (ref "3.3V") (pin "1") (pinfunction "3_1") (pintype "passive"))
      (node (ref "C1") (pin "1") (pinfunction "1_1") (pintype "passive"))
      (node (ref "C2") (pin "1") (pinfunction "1_1") (pintype "passive"))
      (node (ref "C3") (pin "1") (pinfunction "1_1") (pintype "passive"))
      (node (ref "C4") (pin "1") (pinfunction "1_1") (pintype "passive"))
      (node (ref "C5") (pin "1") (pinfunction "1_1") (pintype "passive"))
      (node (ref "C6") (pin "1") (pinfunction "1_1") (pintype "passive"))
      (node (ref "IC3") (pin "22") (pinfunction "PVCC_1_22") (pintype "power_in"))
      (node (ref "IC3") (pin "27") (pinfunction "PVCC_2_27") (pintype "power_in"))
      (node (ref "IC3") (pin "3") (pinfunction "AVCC_3") (pintype "power_in"))
      (node (ref "IC3") (pin "4") (pinfunction "VIO_4") (pintype "input"))
      (node (ref "R18") (pin "1") (pinfunction "1_1") (pintype "passive"))
    )
    (net (code "5") (name "/SCL") (class "Default")
      (node (ref "19_SCL") (pin "1") (pinfunction "3_1") (pintype "passive"))
      (node (ref "IC3") (pin "7") (pinfunction "SCL_7") (pintype "bidirectional"))
    )
    (net (code "6") (name "/SDA") (class "Default")
      (node (ref "18_SDA") (pin "1") (pinfunction "3_1") (pintype "passive"))
      (node (ref "IC3") (pin "6") (pinfunction "SDA_6") (pintype "bidirectional"))
    )
    (net (code "7") (name "GND") (class "Default")
      (node (ref "AMP") (pin "P$2") (pinfunction "3_P$2") (pintype "passive"))
      (node (ref "AMP") (pin "P$3") (pinfunction "1_P$3") (pintype "passive"))
      (node (ref "C1") (pin "2") (pinfunction "2_2") (pintype "passive"))
      (node (ref "C2") (pin "2") (pinfunction "2_2") (pintype "passive"))
      (node (ref "C3") (pin "2") (pinfunction "2_2") (pintype "passive"))
      (node (ref "C4") (pin "2") (pinfunction "2_2") (pintype "passive"))
      (node (ref "C5") (pin "2") (pinfunction "2_2") (pintype "passive"))
      (node (ref "C6") (pin "2") (pinfunction "2_2") (pintype "passive"))
      (node (ref "FREQ") (pin "P$2") (pinfunction "3_P$2") (pintype "passive"))
      (node (ref "FREQ") (pin "P$3") (pinfunction "1_P$3") (pintype "passive"))
      (node (ref "GND9") (pin "1") (pinfunction "3_1") (pintype "passive"))
      (node (ref "IC3") (pin "11") (pinfunction "GND_1_11") (pintype "power_in"))
      (node (ref "IC3") (pin "14") (pinfunction "PGND_1_14") (pintype "power_in"))
      (node (ref "IC3") (pin "18") (pinfunction "PGND_2_18") (pintype "power_in"))
      (node (ref "IC3") (pin "29") (pinfunction "GND_2_29") (pintype "power_in"))
      (node (ref "IC3") (pin "8") (pinfunction "ADDR_8") (pintype "input"))
      (node (ref "OU1") (pin "P$3") (pinfunction "1_P$3") (pintype "passive"))
      (node (ref "OUT2") (pin "P$3") (pinfunction "1_P$3") (pintype "passive"))
      (node (ref "OUT3") (pin "P$3") (pinfunction "1_P$3") (pintype "passive"))
      (node (ref "OUT4") (pin "P$3") (pinfunction "1_P$3") (pintype "passive"))
      (node (ref "OUT5") (pin "P$3") (pinfunction "1_P$3") (pintype "passive"))
      (node (ref "OUT6") (pin "P$3") (pinfunction "1_P$3") (pintype "passive"))
      (node (ref "OUT7") (pin "P$3") (pinfunction "1_P$3") (pintype "passive"))
      (node (ref "OUT8") (pin "P$3") (pinfunction "1_P$3") (pintype "passive"))
      (node (ref "PHASE") (pin "P$2") (pinfunction "3_P$2") (pintype "passive"))
      (node (ref "PHASE") (pin "P$3") (pinfunction "1_P$3") (pintype "passive"))
      (node (ref "R17") (pin "1") (pinfunction "1_1") (pintype "passive"))
      (node (ref "SW1") (pin "C") (pinfunction "C_C") (pintype "passive"))
      (node (ref "SW1") (pin "P1") (pinfunction "1_P1") (pintype "passive"))
      (node (ref "SYNC") (pin "P$2") (pinfunction "3_P$2") (pintype "passive"))
      (node (ref "SYNC") (pin "P$3") (pinfunction "1_P$3") (pintype "passive"))
      (node (ref "TRIG_OUT") (pin "P$3") (pinfunction "1_P$3") (pintype "passive"))
      (node (ref "U1") (pin "1") (pinfunction "~{OE}_1") (pintype "input"))
      (node (ref "U1") (pin "3") (pinfunction "GND_3") (pintype "power_in"))
      (node (ref "WAVE") (pin "P$2") (pinfunction "3_P$2") (pintype "passive"))
      (node (ref "WAVE") (pin "P$3") (pinfunction "1_P$3") (pintype "passive"))
    )
    (net (code "8") (name "Net-(-5V-3)") (class "Default")
      (node (ref "-5V") (pin "1") (pinfunction "3_1") (pintype "passive"))
      (node (ref "VR1") (pin "1") (pinfunction "A_1") (pintype "passive"))
      (node (ref "VR2") (pin "1") (pinfunction "A_1") (pintype "passive"))
      (node (ref "VR3") (pin "1") (pinfunction "A_1") (pintype "passive"))
      (node (ref "VR4") (pin "1") (pinfunction "A_1") (pintype "passive"))
    )
    (net (code "9") (name "Net-(5-3)") (class "Default")
      (node (ref "5") (pin "1") (pinfunction "3_1") (pintype "passive"))
      (node (ref "U1") (pin "2") (pinfunction "A_2") (pintype "input"))
    )
    (net (code "10") (name "Net-(AMP-2)") (class "Default")
      (node (ref "AMP") (pin "P$1") (pinfunction "2_P$1") (pintype "passive"))
      (node (ref "CV5") (pin "1") (pinfunction "3_1") (pintype "passive"))
    )
    (net (code "11") (name "Net-(CV1-3)") (class "Default")
      (node (ref "CV1") (pin "1") (pinfunction "3_1") (pintype "passive"))
      (node (ref "SYNC") (pin "P$1") (pinfunction "2_P$1") (pintype "passive"))
    )
    (net (code "12") (name "Net-(CV2-3)") (class "Default")
      (node (ref "CV2") (pin "1") (pinfunction "3_1") (pintype "passive"))
      (node (ref "WAVE") (pin "P$1") (pinfunction "2_P$1") (pintype "passive"))
    )
    (net (code "13") (name "Net-(CV2_-3)") (class "Default")
      (node (ref "CV2_") (pin "1") (pinfunction "3_1") (pintype "passive"))
      (node (ref "VR3") (pin "2") (pinfunction "S_2") (pintype "passive"))
    )
    (net (code "14") (name "Net-(CV3-3)") (class "Default")
      (node (ref "CV3") (pin "1") (pinfunction "3_1") (pintype "passive"))
      (node (ref "FREQ") (pin "P$1") (pinfunction "2_P$1") (pintype "passive"))
    )
    (net (code "15") (name "Net-(CV3_-3)") (class "Default")
      (node (ref "CV3_") (pin "1") (pinfunction "3_1") (pintype "passive"))
      (node (ref "VR2") (pin "2") (pinfunction "S_2") (pintype "passive"))
    )
    (net (code "16") (name "Net-(CV4-3)") (class "Default")
      (node (ref "CV4") (pin "1") (pinfunction "3_1") (pintype "passive"))
      (node (ref "PHASE") (pin "P$1") (pinfunction "2_P$1") (pintype "passive"))
    )
    (net (code "17") (name "Net-(CV4_-3)") (class "Default")
      (node (ref "CV4_") (pin "1") (pinfunction "3_1") (pintype "passive"))
      (node (ref "VR1") (pin "2") (pinfunction "S_2") (pintype "passive"))
    )
    (net (code "18") (name "Net-(CV5_-3)") (class "Default")
      (node (ref "CV5_") (pin "1") (pinfunction "3_1") (pintype "passive"))
      (node (ref "VR4") (pin "2") (pinfunction "S_2") (pintype "passive"))
    )
    (net (code "19") (name "Net-(CVO1-3)") (class "Default")
      (node (ref "CVO1") (pin "1") (pinfunction "3_1") (pintype "passive"))
      (node (ref "OU1") (pin "P$1") (pinfunction "2_P$1") (pintype "passive"))
    )
    (net (code "20") (name "Net-(CVO2-3)") (class "Default")
      (node (ref "CVO2") (pin "1") (pinfunction "3_1") (pintype "passive"))
      (node (ref "OUT2") (pin "P$1") (pinfunction "2_P$1") (pintype "passive"))
    )
    (net (code "21") (name "Net-(CVO3-3)") (class "Default")
      (node (ref "CVO3") (pin "1") (pinfunction "3_1") (pintype "passive"))
      (node (ref "OUT3") (pin "P$1") (pinfunction "2_P$1") (pintype "passive"))
    )
    (net (code "22") (name "Net-(CVO4-3)") (class "Default")
      (node (ref "CVO4") (pin "1") (pinfunction "3_1") (pintype "passive"))
      (node (ref "OUT4") (pin "P$1") (pinfunction "2_P$1") (pintype "passive"))
    )
    (net (code "23") (name "Net-(CVO5-3)") (class "Default")
      (node (ref "CVO5") (pin "1") (pinfunction "3_1") (pintype "passive"))
      (node (ref "OUT5") (pin "P$1") (pinfunction "2_P$1") (pintype "passive"))
    )
    (net (code "24") (name "Net-(CVO6-3)") (class "Default")
      (node (ref "CVO6") (pin "1") (pinfunction "3_1") (pintype "passive"))
      (node (ref "OUT6") (pin "P$1") (pinfunction "2_P$1") (pintype "passive"))
    )
    (net (code "25") (name "Net-(CVO7-3)") (class "Default")
      (node (ref "CVO7") (pin "1") (pinfunction "3_1") (pintype "passive"))
      (node (ref "OUT7") (pin "P$1") (pinfunction "2_P$1") (pintype "passive"))
    )
    (net (code "26") (name "Net-(CVO8-3)") (class "Default")
      (node (ref "CVO8") (pin "1") (pinfunction "3_1") (pintype "passive"))
      (node (ref "OUT8") (pin "P$1") (pinfunction "2_P$1") (pintype "passive"))
    )
    (net (code "27") (name "Net-(ENC1-3)") (class "Default")
      (node (ref "ENC1") (pin "1") (pinfunction "3_1") (pintype "passive"))
      (node (ref "SW1") (pin "B") (pinfunction "B_B") (pintype "passive"))
    )
    (net (code "28") (name "Net-(ENC2-3)") (class "Default")
      (node (ref "ENC2") (pin "1") (pinfunction "3_1") (pintype "passive"))
      (node (ref "SW1") (pin "A") (pinfunction "A_A") (pintype "passive"))
    )
    (net (code "29") (name "Net-(ENCBTN-3)") (class "Default")
      (node (ref "ENCBTN") (pin "1") (pinfunction "3_1") (pintype "passive"))
      (node (ref "SW1") (pin "P2") (pinfunction "2_P2") (pintype "passive"))
    )
    (net (code "30") (name "Net-(IC3-CS1)") (class "Default")
      (node (ref "IC3") (pin "20") (pinfunction "CS1_20") (pintype "output"))
      (node (ref "LED16") (pin "A") (pinfunction "A_A") (pintype "passive"))
      (node (ref "LED25") (pin "1") (pinfunction "GREEN_ANODE_1") (pintype "passive"))
      (node (ref "LED25") (pin "3") (pinfunction "YELLOW_ANODE_3") (pintype "passive"))
      (node (ref "LED9") (pin "A") (pinfunction "A_A") (pintype "passive"))
    )
    (net (code "31") (name "Net-(IC3-CS2)") (class "Default")
      (node (ref "IC3") (pin "21") (pinfunction "CS2_21") (pintype "output"))
      (node (ref "LED13") (pin "A") (pinfunction "A_A") (pintype "passive"))
      (node (ref "LED15") (pin "A") (pinfunction "A_A") (pintype "passive"))
      (node (ref "LED26") (pin "1") (pinfunction "GREEN_ANODE_1") (pintype "passive"))
      (node (ref "LED26") (pin "3") (pinfunction "YELLOW_ANODE_3") (pintype "passive"))
    )
    (net (code "32") (name "Net-(IC3-CS3)") (class "Default")
      (node (ref "IC3") (pin "23") (pinfunction "CS3_23") (pintype "bidirectional"))
      (node (ref "LED12") (pin "A") (pinfunction "A_A") (pintype "passive"))
      (node (ref "LED14") (pin "A") (pinfunction "A_A") (pintype "passive"))
      (node (ref "LED27") (pin "1") (pinfunction "GREEN_ANODE_1") (pintype "passive"))
      (node (ref "LED27") (pin "3") (pinfunction "YELLOW_ANODE_3") (pintype "passive"))
    )
    (net (code "33") (name "Net-(IC3-CS4)") (class "Default")
      (node (ref "IC3") (pin "24") (pinfunction "CS4_24") (pintype "bidirectional"))
      (node (ref "LED11") (pin "A") (pinfunction "A_A") (pintype "passive"))
      (node (ref "LED21") (pin "A") (pinfunction "A_A") (pintype "passive"))
      (node (ref "LED28") (pin "1") (pinfunction "GREEN_ANODE_1") (pintype "passive"))
      (node (ref "LED28") (pin "3") (pinfunction "YELLOW_ANODE_3") (pintype "passive"))
    )
    (net (code "34") (name "Net-(IC3-CS5)") (class "Default")
      (node (ref "IC3") (pin "25") (pinfunction "CS5_25") (pintype "bidirectional"))
      (node (ref "LED10") (pin "A") (pinfunction "A_A") (pintype "passive"))
      (node (ref "LED22") (pin "A") (pinfunction "A_A") (pintype "passive"))
      (node (ref "LED29") (pin "1") (pinfunction "GREEN_ANODE_1") (pintype "passive"))
      (node (ref "LED29") (pin "3") (pinfunction "YELLOW_ANODE_3") (pintype "passive"))
    )
    (net (code "35") (name "Net-(IC3-CS6)") (class "Default")
      (node (ref "IC3") (pin "26") (pinfunction "CS6_26") (pintype "bidirectional"))
      (node (ref "LED20") (pin "A") (pinfunction "A_A") (pintype "passive"))
      (node (ref "LED23") (pin "A") (pinfunction "A_A") (pintype "passive"))
      (node (ref "LED30") (pin "1") (pinfunction "GREEN_ANODE_1") (pintype "passive"))
      (node (ref "LED30") (pin "3") (pinfunction "YELLOW_ANODE_3") (pintype "passive"))
    )
    (net (code "36") (name "Net-(IC3-CS7)") (class "Default")
      (node (ref "IC3") (pin "28") (pinfunction "CS7_28") (pintype "output"))
      (node (ref "LED19") (pin "A") (pinfunction "A_A") (pintype "passive"))
      (node (ref "LED24") (pin "A") (pinfunction "A_A") (pintype "passive"))
      (node (ref "LED31") (pin "1") (pinfunction "GREEN_ANODE_1") (pintype "passive"))
      (node (ref "LED31") (pin "3") (pinfunction "YELLOW_ANODE_3") (pintype "passive"))
    )
    (net (code "37") (name "Net-(IC3-CS8)") (class "Default")
      (node (ref "IC3") (pin "1") (pinfunction "CS8_1") (pintype "output"))
      (node (ref "LED17") (pin "A") (pinfunction "A_A") (pintype "passive"))
      (node (ref "LED18") (pin "A") (pinfunction "A_A") (pintype "passive"))
      (node (ref "LED32") (pin "1") (pinfunction "GREEN_ANODE_1") (pintype "passive"))
      (node (ref "LED32") (pin "3") (pinfunction "YELLOW_ANODE_3") (pintype "passive"))
    )
    (net (code "38") (name "Net-(IC3-R_EXT)") (class "Default")
      (node (ref "IC3") (pin "2") (pinfunction "R_EXT_2") (pintype "input"))
      (node (ref "R17") (pin "2") (pinfunction "2_2") (pintype "passive"))
    )
    (net (code "39") (name "Net-(IC3-SDB)") (class "Default")
      (node (ref "IC3") (pin "10") (pinfunction "SDB_10") (pintype "input"))
      (node (ref "R18") (pin "2") (pinfunction "2_2") (pintype "passive"))
    )
    (net (code "40") (name "Net-(IC3-SW1)") (class "Default")
      (node (ref "IC3") (pin "12") (pinfunction "SW1_12") (pintype "output"))
      (node (ref "LED25") (pin "4") (pinfunction "YELLOW_CATHODE_4") (pintype "passive"))
      (node (ref "LED26") (pin "4") (pinfunction "YELLOW_CATHODE_4") (pintype "passive"))
      (node (ref "LED27") (pin "4") (pinfunction "YELLOW_CATHODE_4") (pintype "passive"))
      (node (ref "LED28") (pin "4") (pinfunction "YELLOW_CATHODE_4") (pintype "passive"))
      (node (ref "LED29") (pin "4") (pinfunction "YELLOW_CATHODE_4") (pintype "passive"))
      (node (ref "LED30") (pin "4") (pinfunction "YELLOW_CATHODE_4") (pintype "passive"))
      (node (ref "LED31") (pin "4") (pinfunction "YELLOW_CATHODE_4") (pintype "passive"))
      (node (ref "LED32") (pin "4") (pinfunction "YELLOW_CATHODE_4") (pintype "passive"))
    )
    (net (code "41") (name "Net-(IC3-SW2)") (class "Default")
      (node (ref "IC3") (pin "13") (pinfunction "SW2_13") (pintype "output"))
      (node (ref "LED25") (pin "2") (pinfunction "GREEN_CATHODE_2") (pintype "passive"))
      (node (ref "LED26") (pin "2") (pinfunction "GREEN_CATHODE_2") (pintype "passive"))
      (node (ref "LED27") (pin "2") (pinfunction "GREEN_CATHODE_2") (pintype "passive"))
      (node (ref "LED28") (pin "2") (pinfunction "GREEN_CATHODE_2") (pintype "passive"))
      (node (ref "LED29") (pin "2") (pinfunction "GREEN_CATHODE_2") (pintype "passive"))
      (node (ref "LED30") (pin "2") (pinfunction "GREEN_CATHODE_2") (pintype "passive"))
      (node (ref "LED31") (pin "2") (pinfunction "GREEN_CATHODE_2") (pintype "passive"))
      (node (ref "LED32") (pin "2") (pinfunction "GREEN_CATHODE_2") (pintype "passive"))
    )
    (net (code "42") (name "Net-(IC3-SW3)") (class "Default")
      (node (ref "IC3") (pin "15") (pinfunction "SW3_15") (pintype "output"))
      (node (ref "LED10") (pin "C") (pinfunction "C_C") (pintype "passive"))
      (node (ref "LED11") (pin "C") (pinfunction "C_C") (pintype "passive"))
      (node (ref "LED12") (pin "C") (pinfunction "C_C") (pintype "passive"))
      (node (ref "LED13") (pin "C") (pinfunction "C_C") (pintype "passive"))
      (node (ref "LED18") (pin "C") (pinfunction "C_C") (pintype "passive"))
      (node (ref "LED19") (pin "C") (pinfunction "C_C") (pintype "passive"))
      (node (ref "LED20") (pin "C") (pinfunction "C_C") (pintype "passive"))
      (node (ref "LED9") (pin "C") (pinfunction "C_C") (pintype "passive"))
    )
    (net (code "43") (name "Net-(IC3-SW4)") (class "Default")
      (node (ref "IC3") (pin "16") (pinfunction "SW4_16") (pintype "output"))
      (node (ref "LED14") (pin "C") (pinfunction "C_C") (pintype "passive"))
      (node (ref "LED15") (pin "C") (pinfunction "C_C") (pintype "passive"))
      (node (ref "LED16") (pin "C") (pinfunction "C_C") (pintype "passive"))
      (node (ref "LED17") (pin "C") (pinfunction "C_C") (pintype "passive"))
      (node (ref "LED21") (pin "C") (pinfunction "C_C") (pintype "passive"))
      (node (ref "LED22") (pin "C") (pinfunction "C_C") (pintype "passive"))
      (node (ref "LED23") (pin "C") (pinfunction "C_C") (pintype "passive"))
      (node (ref "LED24") (pin "C") (pinfunction "C_C") (pintype "passive"))
    )
    (net (code "44") (name "Net-(TRIG_OUT-2)") (class "Default")
      (node (ref "R56") (pin "1") (pinfunction "1_1") (pintype "passive"))
      (node (ref "TRIG_OUT") (pin "P$1") (pinfunction "2_P$1") (pintype "passive"))
    )
    (net (code "45") (name "Net-(U1A-Y)") (class "Default")
      (node (ref "R56") (pin "2") (pinfunction "2_2") (pintype "passive"))
      (node (ref "U1") (pin "4") (pinfunction "Y_4") (pintype "tri_state"))
    )
    (net (code "46") (name "unconnected-(0_RX-3-Pad1)") (class "Default")
      (node (ref "0_RX") (pin "1") (pinfunction "3_1") (pintype "passive"))
    )
    (net (code "47") (name "unconnected-(1_TX-3-Pad1)") (class "Default")
      (node (ref "1_TX") (pin "1") (pinfunction "3_1") (pintype "passive"))
    )
    (net (code "48") (name "unconnected-(6-3-Pad1)") (class "Default")
      (node (ref "6") (pin "1") (pinfunction "3_1") (pintype "passive"))
    )
    (net (code "49") (name "unconnected-(7-3-Pad1)") (class "Default")
      (node (ref "7") (pin "1") (pinfunction "3_1") (pintype "passive"))
    )
    (net (code "50") (name "unconnected-(10_CS-3-Pad1)") (class "Default")
      (node (ref "10_CS") (pin "1") (pinfunction "3_1") (pintype "passive"))
    )
    (net (code "51") (name "unconnected-(11_MOSI-3-Pad1)") (class "Default")
      (node (ref "11_MOSI") (pin "1") (pinfunction "3_1") (pintype "passive"))
    )
    (net (code "52") (name "unconnected-(12_MISO-3-Pad1)") (class "Default")
      (node (ref "12_MISO") (pin "1") (pinfunction "3_1") (pintype "passive"))
    )
    (net (code "53") (name "unconnected-(13_SCK-3-Pad1)") (class "Default")
      (node (ref "13_SCK") (pin "1") (pinfunction "3_1") (pintype "passive"))
    )
    (net (code "54") (name "unconnected-(28-3-Pad1)") (class "Default")
      (node (ref "28") (pin "1") (pinfunction "3_1") (pintype "passive"))
    )
    (net (code "55") (name "unconnected-(29-3-Pad1)") (class "Default")
      (node (ref "29") (pin "1") (pinfunction "3_1") (pintype "passive"))
    )
    (net (code "56") (name "unconnected-(30-3-Pad1)") (class "Default")
      (node (ref "30") (pin "1") (pinfunction "3_1") (pintype "passive"))
    )
    (net (code "57") (name "unconnected-(31-3-Pad1)") (class "Default")
      (node (ref "31") (pin "1") (pinfunction "3_1") (pintype "passive"))
    )
    (net (code "58") (name "unconnected-(32-3-Pad1)") (class "Default")
      (node (ref "32") (pin "1") (pinfunction "3_1") (pintype "passive"))
    )
    (net (code "59") (name "unconnected-(33-3-Pad1)") (class "Default")
      (node (ref "33") (pin "1") (pinfunction "3_1") (pintype "passive"))
    )
    (net (code "60") (name "unconnected-(34-3-Pad1)") (class "Default")
      (node (ref "34") (pin "1") (pinfunction "3_1") (pintype "passive"))
    )
    (net (code "61") (name "unconnected-(35-3-Pad1)") (class "Default")
      (node (ref "35") (pin "1") (pinfunction "3_1") (pintype "passive"))
    )
    (net (code "62") (name "unconnected-(36-3-Pad1)") (class "Default")
      (node (ref "36") (pin "1") (pinfunction "3_1") (pintype "passive"))
    )
    (net (code "63") (name "unconnected-(37-3-Pad1)") (class "Default")
      (node (ref "37") (pin "1") (pinfunction "3_1") (pintype "passive"))
    )
    (net (code "64") (name "unconnected-(38-3-Pad1)") (class "Default")
      (node (ref "38") (pin "1") (pinfunction "3_1") (pintype "passive"))
    )
    (net (code "65") (name "unconnected-(39-3-Pad1)") (class "Default")
      (node (ref "39") (pin "1") (pinfunction "3_1") (pintype "passive"))
    )
    (net (code "66") (name "unconnected-(40-3-Pad1)") (class "Default")
      (node (ref "40") (pin "1") (pinfunction "3_1") (pintype "passive"))
    )
    (net (code "67") (name "unconnected-(41-3-Pad1)") (class "Default")
      (node (ref "41") (pin "1") (pinfunction "3_1") (pintype "passive"))
    )
    (net (code "68") (name "unconnected-(CV1_-3-Pad1)") (class "Default")
      (node (ref "CV1_") (pin "1") (pinfunction "3_1") (pintype "passive"))
    )
    (net (code "69") (name "unconnected-(CV6-3-Pad1)") (class "Default")
      (node (ref "CV6") (pin "1") (pinfunction "3_1") (pintype "passive"))
    )
    (net (code "70") (name "unconnected-(CV6_-3-Pad1)") (class "Default")
      (node (ref "CV6_") (pin "1") (pinfunction "3_1") (pintype "passive"))
    )
    (net (code "71") (name "unconnected-(CV7-3-Pad1)") (class "Default")
      (node (ref "CV7") (pin "1") (pinfunction "3_1") (pintype "passive"))
    )
    (net (code "72") (name "unconnected-(CV7_-3-Pad1)") (class "Default")
      (node (ref "CV7_") (pin "1") (pinfunction "3_1") (pintype "passive"))
    )
    (net (code "73") (name "unconnected-(CV8-3-Pad1)") (class "Default")
      (node (ref "CV8") (pin "1") (pinfunction "3_1") (pintype "passive"))
    )
    (net (code "74") (name "unconnected-(CV8_-3-Pad1)") (class "Default")
      (node (ref "CV8_") (pin "1") (pinfunction "3_1") (pintype "passive"))
    )
    (net (code "75") (name "unconnected-(CV9-3-Pad1)") (class "Default")
      (node (ref "CV9") (pin "1") (pinfunction "3_1") (pintype "passive"))
    )
    (net (code "76") (name "unconnected-(CV9_-3-Pad1)") (class "Default")
      (node (ref "CV9_") (pin "1") (pinfunction "3_1") (pintype "passive"))
    )
    (net (code "77") (name "unconnected-(CV10-3-Pad1)") (class "Default")
      (node (ref "CV10") (pin "1") (pinfunction "3_1") (pintype "passive"))
    )
    (net (code "78") (name "unconnected-(CV10_-3-Pad1)") (class "Default")
      (node (ref "CV10_") (pin "1") (pinfunction "3_1") (pintype "passive"))
    )
    (net (code "79") (name "unconnected-(CV11-3-Pad1)") (class "Default")
      (node (ref "CV11") (pin "1") (pinfunction "3_1") (pintype "passive"))
    )
    (net (code "80") (name "unconnected-(CV11_-3-Pad1)") (class "Default")
      (node (ref "CV11_") (pin "1") (pinfunction "3_1") (pintype "passive"))
    )
    (net (code "81") (name "unconnected-(CV12-3-Pad1)") (class "Default")
      (node (ref "CV12") (pin "1") (pinfunction "3_1") (pintype "passive"))
    )
    (net (code "82") (name "unconnected-(CV12_-3-Pad1)") (class "Default")
      (node (ref "CV12_") (pin "1") (pinfunction "3_1") (pintype "passive"))
    )
    (net (code "83") (name "unconnected-(D1-A-Pad4)") (class "Default")
      (node (ref "D1") (pin "4") (pinfunction "A_4") (pintype "bidirectional"))
    )
    (net (code "84") (name "unconnected-(D1-BLU-Pad1)") (class "Default")
      (node (ref "D1") (pin "1") (pinfunction "BLU_1") (pintype "bidirectional"))
    )
    (net (code "85") (name "unconnected-(D1-GRN-Pad3)") (class "Default")
      (node (ref "D1") (pin "3") (pinfunction "GRN_3") (pintype "bidirectional"))
    )
    (net (code "86") (name "unconnected-(D1-RED-Pad2)") (class "Default")
      (node (ref "D1") (pin "2") (pinfunction "RED_2") (pintype "bidirectional"))
    )
    (net (code "87") (name "unconnected-(IC3-INTB-Pad9)") (class "Default")
      (node (ref "IC3") (pin "9") (pinfunction "INTB_9") (pintype "input"))
    )
    (net (code "88") (name "unconnected-(IC3-SW5-Pad17)") (class "Default")
      (node (ref "IC3") (pin "17") (pinfunction "SW5_17") (pintype "output"))
    )
    (net (code "89") (name "unconnected-(IC3-SW6-Pad19)") (class "Default")
      (node (ref "IC3") (pin "19") (pinfunction "SW6_19") (pintype "output"))
    )
    (net (code "90") (name "unconnected-(IC3-SYNC-Pad5)") (class "Default")
      (node (ref "IC3") (pin "5") (pinfunction "SYNC_5") (pintype "input"))
    )
    (net (code "91") (name "unconnected-(IO1-3-Pad1)") (class "Default")
      (node (ref "IO1") (pin "1") (pinfunction "3_1") (pintype "passive"))
    )
    (net (code "92") (name "unconnected-(IO2-3-Pad1)") (class "Default")
      (node (ref "IO2") (pin "1") (pinfunction "3_1") (pintype "passive"))
    )
    (net (code "93") (name "unconnected-(IO3-3-Pad1)") (class "Default")
      (node (ref "IO3") (pin "1") (pinfunction "3_1") (pintype "passive"))
    )
    (net (code "94") (name "unconnected-(IO4-3-Pad1)") (class "Default")
      (node (ref "IO4") (pin "1") (pinfunction "3_1") (pintype "passive"))
    )
    (net (code "95") (name "unconnected-(IO5-3-Pad1)") (class "Default")
      (node (ref "IO5") (pin "1") (pinfunction "3_1") (pintype "passive"))
    )
    (net (code "96") (name "unconnected-(IO6-3-Pad1)") (class "Default")
      (node (ref "IO6") (pin "1") (pinfunction "3_1") (pintype "passive"))
    )
    (net (code "97") (name "unconnected-(IO7-3-Pad1)") (class "Default")
      (node (ref "IO7") (pin "1") (pinfunction "3_1") (pintype "passive"))
    )
    (net (code "98") (name "unconnected-(IO8-3-Pad1)") (class "Default")
      (node (ref "IO8") (pin "1") (pinfunction "3_1") (pintype "passive"))
    )
    (net (code "99") (name "unconnected-(IO9-3-Pad1)") (class "Default")
      (node (ref "IO9") (pin "1") (pinfunction "3_1") (pintype "passive"))
    )
    (net (code "100") (name "unconnected-(IO10-3-Pad1)") (class "Default")
      (node (ref "IO10") (pin "1") (pinfunction "3_1") (pintype "passive"))
    )
    (net (code "101") (name "unconnected-(IO11-3-Pad1)") (class "Default")
      (node (ref "IO11") (pin "1") (pinfunction "3_1") (pintype "passive"))
    )
    (net (code "102") (name "unconnected-(IO12-3-Pad1)") (class "Default")
      (node (ref "IO12") (pin "1") (pinfunction "3_1") (pintype "passive"))
    )
    (net (code "103") (name "unconnected-(IO13-3-Pad1)") (class "Default")
      (node (ref "IO13") (pin "1") (pinfunction "3_1") (pintype "passive"))
    )
    (net (code "104") (name "unconnected-(IO14-3-Pad1)") (class "Default")
      (node (ref "IO14") (pin "1") (pinfunction "3_1") (pintype "passive"))
    )
    (net (code "105") (name "unconnected-(IO15-3-Pad1)") (class "Default")
      (node (ref "IO15") (pin "1") (pinfunction "3_1") (pintype "passive"))
    )
    (net (code "106") (name "unconnected-(IO16-3-Pad1)") (class "Default")
      (node (ref "IO16") (pin "1") (pinfunction "3_1") (pintype "passive"))
    )
    (net (code "107") (name "unconnected-(OU1-3-PadP$2)") (class "Default")
      (node (ref "OU1") (pin "P$2") (pinfunction "3_P$2") (pintype "passive"))
    )
    (net (code "108") (name "unconnected-(OUT2-3-PadP$2)") (class "Default")
      (node (ref "OUT2") (pin "P$2") (pinfunction "3_P$2") (pintype "passive"))
    )
    (net (code "109") (name "unconnected-(OUT3-3-PadP$2)") (class "Default")
      (node (ref "OUT3") (pin "P$2") (pinfunction "3_P$2") (pintype "passive"))
    )
    (net (code "110") (name "unconnected-(OUT4-3-PadP$2)") (class "Default")
      (node (ref "OUT4") (pin "P$2") (pinfunction "3_P$2") (pintype "passive"))
    )
    (net (code "111") (name "unconnected-(OUT5-3-PadP$2)") (class "Default")
      (node (ref "OUT5") (pin "P$2") (pinfunction "3_P$2") (pintype "passive"))
    )
    (net (code "112") (name "unconnected-(OUT6-3-PadP$2)") (class "Default")
      (node (ref "OUT6") (pin "P$2") (pinfunction "3_P$2") (pintype "passive"))
    )
    (net (code "113") (name "unconnected-(OUT7-3-PadP$2)") (class "Default")
      (node (ref "OUT7") (pin "P$2") (pinfunction "3_P$2") (pintype "passive"))
    )
    (net (code "114") (name "unconnected-(OUT8-3-PadP$2)") (class "Default")
      (node (ref "OUT8") (pin "P$2") (pinfunction "3_P$2") (pintype "passive"))
    )
    (net (code "115") (name "unconnected-(TRIG_OUT-3-PadP$2)") (class "Default")
      (node (ref "TRIG_OUT") (pin "P$2") (pinfunction "3_P$2") (pintype "passive"))
    )
  )
)
